# AudioControllerSchematic_Final.net
KiCad netlist of a schematic drawn in EAGLE
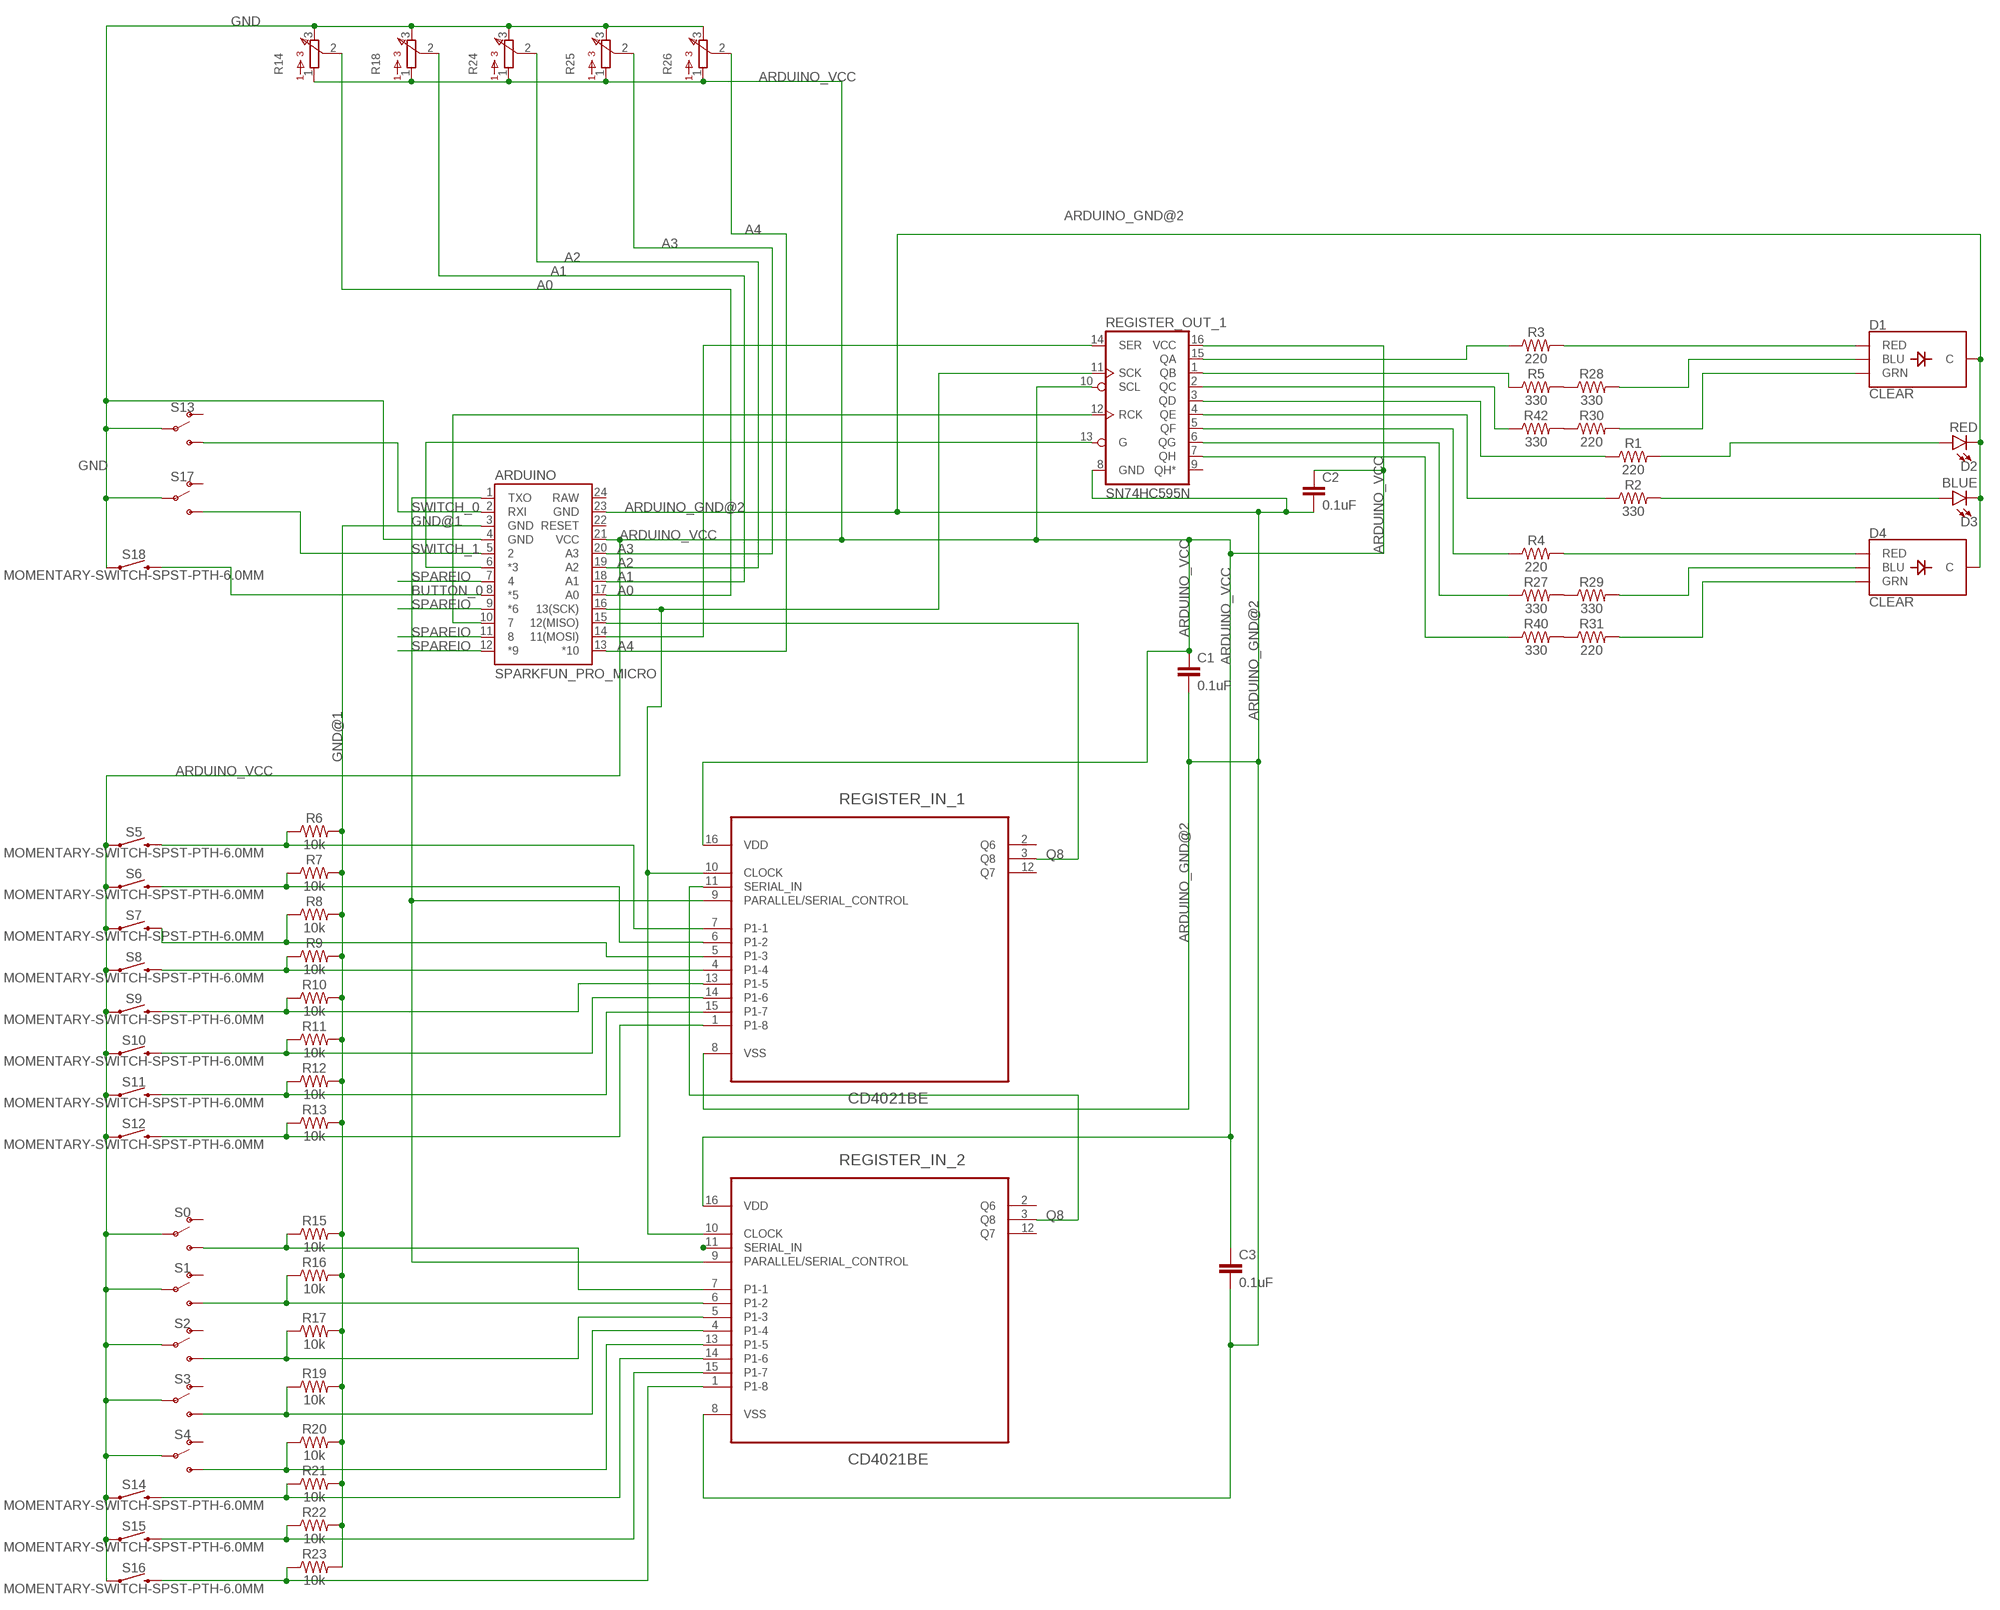
[diagram p0: schematic, sheet 1]

(export (version "E")
  (design (tool "Eeschema 10.0.6"))
  (components
    (comp (ref "ARDUINO")
      (value "SPARKFUN_PRO_MICRO")
      (footprint "eagle-import:SPARKFUN_PRO_MICRO")
      (libsource (lib "eagle-import") (part "SPARKFUN_PRO_MICRO"))
    )
    (comp (ref "C1")
      (value "0.1uF")
      (footprint "eagle-import:0402")
      (libsource (lib "eagle-import") (part "0.1UF-0402-16V-10%"))
    )
    (comp (ref "C2")
      (value "0.1uF")
      (footprint "eagle-import:0402")
      (libsource (lib "eagle-import") (part "0.1UF-0402-16V-10%"))
    )
    (comp (ref "C3")
      (value "0.1uF")
      (footprint "eagle-import:0402")
      (libsource (lib "eagle-import") (part "0.1UF-0402-16V-10%"))
    )
    (comp (ref "D1")
      (value "CLEAR")
      (footprint "eagle-import:LED-RGB-THRU")
      (libsource (lib "eagle-import") (part "LED-RGB-CCCLEAR"))
    )
    (comp (ref "D2")
      (value "RED")
      (footprint "eagle-import:LED-0603")
      (libsource (lib "eagle-import") (part "LED-RED0603"))
    )
    (comp (ref "D3")
      (value "BLUE")
      (footprint "eagle-import:LED-0603")
      (libsource (lib "eagle-import") (part "LED-BLUE0603"))
    )
    (comp (ref "D4")
      (value "CLEAR")
      (footprint "eagle-import:LED-RGB-THRU")
      (libsource (lib "eagle-import") (part "LED-RGB-CCCLEAR"))
    )
    (comp (ref "R1")
      (value "220")
      (footprint "eagle-import:0603")
      (libsource (lib "eagle-import") (part "220OHM-0603-1/10W-1%"))
    )
    (comp (ref "R2")
      (value "330")
      (footprint "eagle-import:0603")
      (libsource (lib "eagle-import") (part "330OHM-0603-1/10W-1%"))
    )
    (comp (ref "R3")
      (value "220")
      (footprint "eagle-import:0603")
      (libsource (lib "eagle-import") (part "220OHM-0603-1/10W-1%"))
    )
    (comp (ref "R4")
      (value "220")
      (footprint "eagle-import:0603")
      (libsource (lib "eagle-import") (part "220OHM-0603-1/10W-1%"))
    )
    (comp (ref "R5")
      (value "330")
      (footprint "eagle-import:0603")
      (libsource (lib "eagle-import") (part "330OHM-0603-1/10W-1%"))
    )
    (comp (ref "R6")
      (value "10k")
      (footprint "eagle-import:0603")
      (libsource (lib "eagle-import") (part "10KOHM-0603-1/10W-1%"))
    )
    (comp (ref "R7")
      (value "10k")
      (footprint "eagle-import:0603")
      (libsource (lib "eagle-import") (part "10KOHM-0603-1/10W-1%"))
    )
    (comp (ref "R8")
      (value "10k")
      (footprint "eagle-import:0603")
      (libsource (lib "eagle-import") (part "10KOHM-0603-1/10W-1%"))
    )
    (comp (ref "R9")
      (value "10k")
      (footprint "eagle-import:0603")
      (libsource (lib "eagle-import") (part "10KOHM-0603-1/10W-1%"))
    )
    (comp (ref "R10")
      (value "10k")
      (footprint "eagle-import:0603")
      (libsource (lib "eagle-import") (part "10KOHM-0603-1/10W-1%"))
    )
    (comp (ref "R11")
      (value "10k")
      (footprint "eagle-import:0603")
      (libsource (lib "eagle-import") (part "10KOHM-0603-1/10W-1%"))
    )
    (comp (ref "R12")
      (value "10k")
      (footprint "eagle-import:0603")
      (libsource (lib "eagle-import") (part "10KOHM-0603-1/10W-1%"))
    )
    (comp (ref "R13")
      (value "10k")
      (footprint "eagle-import:0603")
      (libsource (lib "eagle-import") (part "10KOHM-0603-1/10W-1%"))
    )
    (comp (ref "R14") (value "91") (footprint "eagle-import:91") (libsource (lib "eagle-import") (part "91")))
    (comp (ref "R15")
      (value "10k")
      (footprint "eagle-import:0603")
      (libsource (lib "eagle-import") (part "10KOHM-0603-1/10W-1%"))
    )
    (comp (ref "R16")
      (value "10k")
      (footprint "eagle-import:0603")
      (libsource (lib "eagle-import") (part "10KOHM-0603-1/10W-1%"))
    )
    (comp (ref "R17")
      (value "10k")
      (footprint "eagle-import:0603")
      (libsource (lib "eagle-import") (part "10KOHM-0603-1/10W-1%"))
    )
    (comp (ref "R18") (value "91") (footprint "eagle-import:91") (libsource (lib "eagle-import") (part "91")))
    (comp (ref "R19")
      (value "10k")
      (footprint "eagle-import:0603")
      (libsource (lib "eagle-import") (part "10KOHM-0603-1/10W-1%"))
    )
    (comp (ref "R20")
      (value "10k")
      (footprint "eagle-import:0603")
      (libsource (lib "eagle-import") (part "10KOHM-0603-1/10W-1%"))
    )
    (comp (ref "R21")
      (value "10k")
      (footprint "eagle-import:0603")
      (libsource (lib "eagle-import") (part "10KOHM-0603-1/10W-1%"))
    )
    (comp (ref "R22")
      (value "10k")
      (footprint "eagle-import:0603")
      (libsource (lib "eagle-import") (part "10KOHM-0603-1/10W-1%"))
    )
    (comp (ref "R23")
      (value "10k")
      (footprint "eagle-import:0603")
      (libsource (lib "eagle-import") (part "10KOHM-0603-1/10W-1%"))
    )
    (comp (ref "R24") (value "91") (footprint "eagle-import:91") (libsource (lib "eagle-import") (part "91")))
    (comp (ref "R25") (value "91") (footprint "eagle-import:91") (libsource (lib "eagle-import") (part "91")))
    (comp (ref "R26") (value "91") (footprint "eagle-import:91") (libsource (lib "eagle-import") (part "91")))
    (comp (ref "R27")
      (value "330")
      (footprint "eagle-import:0603")
      (libsource (lib "eagle-import") (part "330OHM-0603-1/10W-1%"))
    )
    (comp (ref "R28")
      (value "330")
      (footprint "eagle-import:0603")
      (libsource (lib "eagle-import") (part "330OHM-0603-1/10W-1%"))
    )
    (comp (ref "R29")
      (value "330")
      (footprint "eagle-import:0603")
      (libsource (lib "eagle-import") (part "330OHM-0603-1/10W-1%"))
    )
    (comp (ref "R30")
      (value "220")
      (footprint "eagle-import:0603")
      (libsource (lib "eagle-import") (part "220OHM-0603-1/10W-1%"))
    )
    (comp (ref "R31")
      (value "220")
      (footprint "eagle-import:0603")
      (libsource (lib "eagle-import") (part "220OHM-0603-1/10W-1%"))
    )
    (comp (ref "R40")
      (value "330")
      (footprint "eagle-import:0603")
      (libsource (lib "eagle-import") (part "330OHM-0603-1/10W-1%"))
    )
    (comp (ref "R42")
      (value "330")
      (footprint "eagle-import:0603")
      (libsource (lib "eagle-import") (part "330OHM-0603-1/10W-1%"))
    )
    (comp (ref "REGISTER_IN_1")
      (value "CD4021BE")
      (footprint "eagle-import:DIP254P762X508-16")
      (fields (field (name "MF") "Texas"))
      (libsource (lib "eagle-import") (part "CD4021BE"))
    )
    (comp (ref "REGISTER_IN_2")
      (value "CD4021BE")
      (footprint "eagle-import:DIP254P762X508-16")
      (fields (field (name "MF") "Texas"))
      (libsource (lib "eagle-import") (part "CD4021BE"))
    )
    (comp (ref "REGISTER_OUT_1")
      (value "SN74HC595N")
      (footprint "eagle-import:DIP16")
      (libsource (lib "eagle-import") (part "74595NHC"))
    )
    (comp (ref "S0")
      (value "SWITCH-SPDT-PTH-11.6X4.0MM")
      (footprint "eagle-import:SWITCH_SPDT_PTH_11.6X4.0MM")
      (libsource (lib "eagle-import") (part "SWITCH-SPDT-PTH-11.6X4.0MM"))
    )
    (comp (ref "S1")
      (value "SWITCH-SPDT-PTH-11.6X4.0MM")
      (footprint "eagle-import:SWITCH_SPDT_PTH_11.6X4.0MM")
      (libsource (lib "eagle-import") (part "SWITCH-SPDT-PTH-11.6X4.0MM"))
    )
    (comp (ref "S2")
      (value "SWITCH-SPDT-PTH-11.6X4.0MM")
      (footprint "eagle-import:SWITCH_SPDT_PTH_11.6X4.0MM")
      (libsource (lib "eagle-import") (part "SWITCH-SPDT-PTH-11.6X4.0MM"))
    )
    (comp (ref "S3")
      (value "SWITCH-SPDT-PTH-11.6X4.0MM")
      (footprint "eagle-import:SWITCH_SPDT_PTH_11.6X4.0MM")
      (libsource (lib "eagle-import") (part "SWITCH-SPDT-PTH-11.6X4.0MM"))
    )
    (comp (ref "S4")
      (value "SWITCH-SPDT-PTH-11.6X4.0MM")
      (footprint "eagle-import:SWITCH_SPDT_PTH_11.6X4.0MM")
      (libsource (lib "eagle-import") (part "SWITCH-SPDT-PTH-11.6X4.0MM"))
    )
    (comp (ref "S5")
      (value "MOMENTARY-SWITCH-SPST-PTH-6.0MM")
      (footprint "eagle-import:TACTILE_SWITCH_PTH_6.0MM")
      (libsource (lib "eagle-import") (part "MOMENTARY-SWITCH-SPST-PTH-6.0MM"))
    )
    (comp (ref "S6")
      (value "MOMENTARY-SWITCH-SPST-PTH-6.0MM")
      (footprint "eagle-import:TACTILE_SWITCH_PTH_6.0MM")
      (libsource (lib "eagle-import") (part "MOMENTARY-SWITCH-SPST-PTH-6.0MM"))
    )
    (comp (ref "S7")
      (value "MOMENTARY-SWITCH-SPST-PTH-6.0MM")
      (footprint "eagle-import:TACTILE_SWITCH_PTH_6.0MM")
      (libsource (lib "eagle-import") (part "MOMENTARY-SWITCH-SPST-PTH-6.0MM"))
    )
    (comp (ref "S8")
      (value "MOMENTARY-SWITCH-SPST-PTH-6.0MM")
      (footprint "eagle-import:TACTILE_SWITCH_PTH_6.0MM")
      (libsource (lib "eagle-import") (part "MOMENTARY-SWITCH-SPST-PTH-6.0MM"))
    )
    (comp (ref "S9")
      (value "MOMENTARY-SWITCH-SPST-PTH-6.0MM")
      (footprint "eagle-import:TACTILE_SWITCH_PTH_6.0MM")
      (libsource (lib "eagle-import") (part "MOMENTARY-SWITCH-SPST-PTH-6.0MM"))
    )
    (comp (ref "S10")
      (value "MOMENTARY-SWITCH-SPST-PTH-6.0MM")
      (footprint "eagle-import:TACTILE_SWITCH_PTH_6.0MM")
      (libsource (lib "eagle-import") (part "MOMENTARY-SWITCH-SPST-PTH-6.0MM"))
    )
    (comp (ref "S11")
      (value "MOMENTARY-SWITCH-SPST-PTH-6.0MM")
      (footprint "eagle-import:TACTILE_SWITCH_PTH_6.0MM")
      (libsource (lib "eagle-import") (part "MOMENTARY-SWITCH-SPST-PTH-6.0MM"))
    )
    (comp (ref "S12")
      (value "MOMENTARY-SWITCH-SPST-PTH-6.0MM")
      (footprint "eagle-import:TACTILE_SWITCH_PTH_6.0MM")
      (libsource (lib "eagle-import") (part "MOMENTARY-SWITCH-SPST-PTH-6.0MM"))
    )
    (comp (ref "S13")
      (value "SWITCH-SPDT-PTH-11.6X4.0MM")
      (footprint "eagle-import:SWITCH_SPDT_PTH_11.6X4.0MM")
      (libsource (lib "eagle-import") (part "SWITCH-SPDT-PTH-11.6X4.0MM"))
    )
    (comp (ref "S14")
      (value "MOMENTARY-SWITCH-SPST-PTH-6.0MM")
      (footprint "eagle-import:TACTILE_SWITCH_PTH_6.0MM")
      (libsource (lib "eagle-import") (part "MOMENTARY-SWITCH-SPST-PTH-6.0MM"))
    )
    (comp (ref "S15")
      (value "MOMENTARY-SWITCH-SPST-PTH-6.0MM")
      (footprint "eagle-import:TACTILE_SWITCH_PTH_6.0MM")
      (libsource (lib "eagle-import") (part "MOMENTARY-SWITCH-SPST-PTH-6.0MM"))
    )
    (comp (ref "S16")
      (value "MOMENTARY-SWITCH-SPST-PTH-6.0MM")
      (footprint "eagle-import:TACTILE_SWITCH_PTH_6.0MM")
      (libsource (lib "eagle-import") (part "MOMENTARY-SWITCH-SPST-PTH-6.0MM"))
    )
    (comp (ref "S17")
      (value "SWITCH-SPDT-PTH-11.6X4.0MM")
      (footprint "eagle-import:SWITCH_SPDT_PTH_11.6X4.0MM")
      (libsource (lib "eagle-import") (part "SWITCH-SPDT-PTH-11.6X4.0MM"))
    )
    (comp (ref "S18")
      (value "MOMENTARY-SWITCH-SPST-PTH-6.0MM")
      (footprint "eagle-import:TACTILE_SWITCH_PTH_6.0MM")
      (libsource (lib "eagle-import") (part "MOMENTARY-SWITCH-SPST-PTH-6.0MM"))
    )
  )
  (nets
    (net (code "1") (name "/A0") (class "Default")
      (node (ref "ARDUINO") (pin "17") (pinfunction "A0_17") (pintype "bidirectional"))
      (node (ref "R14") (pin "2") (pinfunction "2_2") (pintype "passive"))
    )
    (net (code "2") (name "/A1") (class "Default")
      (node (ref "ARDUINO") (pin "18") (pinfunction "A1_18") (pintype "bidirectional"))
      (node (ref "R18") (pin "2") (pinfunction "2_2") (pintype "passive"))
    )
    (net (code "3") (name "/A2") (class "Default")
      (node (ref "ARDUINO") (pin "19") (pinfunction "A2_19") (pintype "bidirectional"))
      (node (ref "R24") (pin "2") (pinfunction "2_2") (pintype "passive"))
    )
    (net (code "4") (name "/A3") (class "Default")
      (node (ref "ARDUINO") (pin "20") (pinfunction "A3_20") (pintype "bidirectional"))
      (node (ref "R25") (pin "2") (pinfunction "2_2") (pintype "passive"))
    )
    (net (code "5") (name "/A4") (class "Default")
      (node (ref "ARDUINO") (pin "13") (pinfunction "*10_13") (pintype "bidirectional"))
      (node (ref "R26") (pin "2") (pinfunction "2_2") (pintype "passive"))
    )
    (net (code "6") (name "/ARDUINO_GND@2") (class "Default")
      (node (ref "ARDUINO") (pin "23") (pinfunction "GND_23") (pintype "power_in"))
      (node (ref "C1") (pin "2") (pinfunction "2_2") (pintype "passive"))
      (node (ref "C2") (pin "2") (pinfunction "2_2") (pintype "passive"))
      (node (ref "C3") (pin "2") (pinfunction "2_2") (pintype "passive"))
      (node (ref "D1") (pin "2") (pinfunction "C_2") (pintype "bidirectional"))
      (node (ref "D2") (pin "C") (pinfunction "C_C") (pintype "passive"))
      (node (ref "D3") (pin "C") (pinfunction "C_C") (pintype "passive"))
      (node (ref "D4") (pin "2") (pinfunction "C_2") (pintype "bidirectional"))
      (node (ref "REGISTER_IN_1") (pin "8") (pinfunction "VSS_8") (pintype "passive"))
      (node (ref "REGISTER_IN_2") (pin "8") (pinfunction "VSS_8") (pintype "passive"))
      (node (ref "REGISTER_OUT_1") (pin "8") (pinfunction "GND_8") (pintype "power_in"))
    )
    (net (code "7") (name "/ARDUINO_VCC") (class "Default")
      (node (ref "ARDUINO") (pin "21") (pinfunction "VCC_21") (pintype "power_in"))
      (node (ref "C1") (pin "1") (pinfunction "1_1") (pintype "passive"))
      (node (ref "C2") (pin "1") (pinfunction "1_1") (pintype "passive"))
      (node (ref "C3") (pin "1") (pinfunction "1_1") (pintype "passive"))
      (node (ref "R14") (pin "1") (pinfunction "1_1") (pintype "passive"))
      (node (ref "R18") (pin "1") (pinfunction "1_1") (pintype "passive"))
      (node (ref "R24") (pin "1") (pinfunction "1_1") (pintype "passive"))
      (node (ref "R25") (pin "1") (pinfunction "1_1") (pintype "passive"))
      (node (ref "R26") (pin "1") (pinfunction "1_1") (pintype "passive"))
      (node (ref "REGISTER_IN_1") (pin "16") (pinfunction "VDD_16") (pintype "power_in"))
      (node (ref "REGISTER_IN_2") (pin "16") (pinfunction "VDD_16") (pintype "power_in"))
      (node (ref "REGISTER_OUT_1") (pin "10") (pinfunction "SCL_10") (pintype "input"))
      (node (ref "REGISTER_OUT_1") (pin "16") (pinfunction "VCC_16") (pintype "power_in"))
      (node (ref "S0") (pin "2") (pinfunction "P_2") (pintype "passive"))
      (node (ref "S1") (pin "2") (pinfunction "P_2") (pintype "passive"))
      (node (ref "S10") (pin "1") (pinfunction "1_1") (pintype "passive"))
      (node (ref "S11") (pin "1") (pinfunction "1_1") (pintype "passive"))
      (node (ref "S12") (pin "1") (pinfunction "1_1") (pintype "passive"))
      (node (ref "S14") (pin "1") (pinfunction "1_1") (pintype "passive"))
      (node (ref "S15") (pin "1") (pinfunction "1_1") (pintype "passive"))
      (node (ref "S16") (pin "1") (pinfunction "1_1") (pintype "passive"))
      (node (ref "S2") (pin "2") (pinfunction "P_2") (pintype "passive"))
      (node (ref "S3") (pin "2") (pinfunction "P_2") (pintype "passive"))
      (node (ref "S4") (pin "2") (pinfunction "P_2") (pintype "passive"))
      (node (ref "S5") (pin "1") (pinfunction "1_1") (pintype "passive"))
      (node (ref "S6") (pin "1") (pinfunction "1_1") (pintype "passive"))
      (node (ref "S7") (pin "1") (pinfunction "1_1") (pintype "passive"))
      (node (ref "S8") (pin "1") (pinfunction "1_1") (pintype "passive"))
      (node (ref "S9") (pin "1") (pinfunction "1_1") (pintype "passive"))
    )
    (net (code "8") (name "/BUTTON_0") (class "Default")
      (node (ref "ARDUINO") (pin "8") (pinfunction "*5_8") (pintype "bidirectional"))
      (node (ref "S18") (pin "3") (pinfunction "2_3") (pintype "passive"))
    )
    (net (code "9") (name "/GND") (class "Default")
      (node (ref "ARDUINO") (pin "4") (pinfunction "GND_4") (pintype "power_in"))
      (node (ref "R14") (pin "3") (pinfunction "3_3") (pintype "passive"))
      (node (ref "R18") (pin "3") (pinfunction "3_3") (pintype "passive"))
      (node (ref "R24") (pin "3") (pinfunction "3_3") (pintype "passive"))
      (node (ref "R25") (pin "3") (pinfunction "3_3") (pintype "passive"))
      (node (ref "R26") (pin "3") (pinfunction "3_3") (pintype "passive"))
      (node (ref "S13") (pin "2") (pinfunction "P_2") (pintype "passive"))
      (node (ref "S17") (pin "2") (pinfunction "P_2") (pintype "passive"))
      (node (ref "S18") (pin "1") (pinfunction "1_1") (pintype "passive"))
    )
    (net (code "10") (name "/GND@1") (class "Default")
      (node (ref "ARDUINO") (pin "3") (pinfunction "GND_3") (pintype "power_in"))
      (node (ref "R10") (pin "2") (pinfunction "2_2") (pintype "passive"))
      (node (ref "R11") (pin "2") (pinfunction "2_2") (pintype "passive"))
      (node (ref "R12") (pin "2") (pinfunction "2_2") (pintype "passive"))
      (node (ref "R13") (pin "2") (pinfunction "2_2") (pintype "passive"))
      (node (ref "R15") (pin "2") (pinfunction "2_2") (pintype "passive"))
      (node (ref "R16") (pin "2") (pinfunction "2_2") (pintype "passive"))
      (node (ref "R17") (pin "2") (pinfunction "2_2") (pintype "passive"))
      (node (ref "R19") (pin "2") (pinfunction "2_2") (pintype "passive"))
      (node (ref "R20") (pin "2") (pinfunction "2_2") (pintype "passive"))
      (node (ref "R21") (pin "2") (pinfunction "2_2") (pintype "passive"))
      (node (ref "R22") (pin "2") (pinfunction "2_2") (pintype "passive"))
      (node (ref "R23") (pin "2") (pinfunction "2_2") (pintype "passive"))
      (node (ref "R6") (pin "2") (pinfunction "2_2") (pintype "passive"))
      (node (ref "R7") (pin "2") (pinfunction "2_2") (pintype "passive"))
      (node (ref "R8") (pin "2") (pinfunction "2_2") (pintype "passive"))
      (node (ref "R9") (pin "2") (pinfunction "2_2") (pintype "passive"))
    )
    (net (code "11") (name "/Q8") (class "Default")
      (node (ref "ARDUINO") (pin "15") (pinfunction "12(MISO)_15") (pintype "bidirectional"))
      (node (ref "REGISTER_IN_1") (pin "11") (pinfunction "SERIAL_IN_11") (pintype "input"))
      (node (ref "REGISTER_IN_1") (pin "3") (pinfunction "Q8_3") (pintype "output"))
      (node (ref "REGISTER_IN_2") (pin "3") (pinfunction "Q8_3") (pintype "output"))
    )
    (net (code "12") (name "/RAW") (class "Default")
      (node (ref "ARDUINO") (pin "24") (pinfunction "RAW_24") (pintype "power_in"))
    )
    (net (code "13") (name "/SPAREIO") (class "Default")
      (node (ref "ARDUINO") (pin "11") (pinfunction "8_11") (pintype "bidirectional"))
      (node (ref "ARDUINO") (pin "12") (pinfunction "*9_12") (pintype "bidirectional"))
      (node (ref "ARDUINO") (pin "7") (pinfunction "4_7") (pintype "bidirectional"))
      (node (ref "ARDUINO") (pin "9") (pinfunction "*6_9") (pintype "bidirectional"))
    )
    (net (code "14") (name "/SWITCH_0") (class "Default")
      (node (ref "ARDUINO") (pin "2") (pinfunction "RXI_2") (pintype "bidirectional"))
      (node (ref "S13") (pin "3") (pinfunction "S_3") (pintype "passive"))
    )
    (net (code "15") (name "/SWITCH_1") (class "Default")
      (node (ref "ARDUINO") (pin "5") (pinfunction "2_5") (pintype "bidirectional"))
      (node (ref "S17") (pin "3") (pinfunction "S_3") (pintype "passive"))
    )
    (net (code "16") (name "Net-(ARDUINO-*3)") (class "Default")
      (node (ref "ARDUINO") (pin "6") (pinfunction "*3_6") (pintype "bidirectional"))
      (node (ref "REGISTER_OUT_1") (pin "13") (pinfunction "G_13") (pintype "input"))
    )
    (net (code "17") (name "Net-(ARDUINO-7)") (class "Default")
      (node (ref "ARDUINO") (pin "10") (pinfunction "7_10") (pintype "bidirectional"))
      (node (ref "REGISTER_OUT_1") (pin "12") (pinfunction "RCK_12") (pintype "input"))
    )
    (net (code "18") (name "Net-(ARDUINO-11(MOSI))") (class "Default")
      (node (ref "ARDUINO") (pin "14") (pinfunction "11(MOSI)_14") (pintype "bidirectional"))
      (node (ref "REGISTER_OUT_1") (pin "14") (pinfunction "SER_14") (pintype "input"))
    )
    (net (code "19") (name "Net-(ARDUINO-13(SCK))") (class "Default")
      (node (ref "ARDUINO") (pin "16") (pinfunction "13(SCK)_16") (pintype "bidirectional"))
      (node (ref "REGISTER_IN_1") (pin "10") (pinfunction "CLOCK_10") (pintype "input"))
      (node (ref "REGISTER_IN_2") (pin "10") (pinfunction "CLOCK_10") (pintype "input"))
      (node (ref "REGISTER_OUT_1") (pin "11") (pinfunction "SCK_11") (pintype "input"))
    )
    (net (code "20") (name "Net-(ARDUINO-TXO)") (class "Default")
      (node (ref "ARDUINO") (pin "1") (pinfunction "TXO_1") (pintype "bidirectional"))
      (node (ref "REGISTER_IN_1") (pin "9") (pinfunction "PARALLEL/SERIAL_CONTROL_9") (pintype "input"))
      (node (ref "REGISTER_IN_2") (pin "9") (pinfunction "PARALLEL/SERIAL_CONTROL_9") (pintype "input"))
    )
    (net (code "21") (name "Net-(D1-BLU)") (class "Default")
      (node (ref "D1") (pin "4") (pinfunction "BLU_4") (pintype "bidirectional"))
      (node (ref "R28") (pin "2") (pinfunction "2_2") (pintype "passive"))
    )
    (net (code "22") (name "Net-(D1-GRN)") (class "Default")
      (node (ref "D1") (pin "3") (pinfunction "GRN_3") (pintype "bidirectional"))
      (node (ref "R30") (pin "2") (pinfunction "2_2") (pintype "passive"))
    )
    (net (code "23") (name "Net-(D1-RED)") (class "Default")
      (node (ref "D1") (pin "1") (pinfunction "RED_1") (pintype "bidirectional"))
      (node (ref "R3") (pin "2") (pinfunction "2_2") (pintype "passive"))
    )
    (net (code "24") (name "Net-(D2-PadA)") (class "Default")
      (node (ref "D2") (pin "A") (pinfunction "A_A") (pintype "passive"))
      (node (ref "R1") (pin "2") (pinfunction "2_2") (pintype "passive"))
    )
    (net (code "25") (name "Net-(D3-PadA)") (class "Default")
      (node (ref "D3") (pin "A") (pinfunction "A_A") (pintype "passive"))
      (node (ref "R2") (pin "2") (pinfunction "2_2") (pintype "passive"))
    )
    (net (code "26") (name "Net-(D4-BLU)") (class "Default")
      (node (ref "D4") (pin "4") (pinfunction "BLU_4") (pintype "bidirectional"))
      (node (ref "R29") (pin "2") (pinfunction "2_2") (pintype "passive"))
    )
    (net (code "27") (name "Net-(D4-GRN)") (class "Default")
      (node (ref "D4") (pin "3") (pinfunction "GRN_3") (pintype "bidirectional"))
      (node (ref "R31") (pin "2") (pinfunction "2_2") (pintype "passive"))
    )
    (net (code "28") (name "Net-(D4-RED)") (class "Default")
      (node (ref "D4") (pin "1") (pinfunction "RED_1") (pintype "bidirectional"))
      (node (ref "R4") (pin "2") (pinfunction "2_2") (pintype "passive"))
    )
    (net (code "29") (name "Net-(R27-Pad2)") (class "Default")
      (node (ref "R27") (pin "2") (pinfunction "2_2") (pintype "passive"))
      (node (ref "R29") (pin "1") (pinfunction "1_1") (pintype "passive"))
    )
    (net (code "30") (name "Net-(R28-Pad1)") (class "Default")
      (node (ref "R28") (pin "1") (pinfunction "1_1") (pintype "passive"))
      (node (ref "R5") (pin "2") (pinfunction "2_2") (pintype "passive"))
    )
    (net (code "31") (name "Net-(R30-Pad1)") (class "Default")
      (node (ref "R30") (pin "1") (pinfunction "1_1") (pintype "passive"))
      (node (ref "R42") (pin "2") (pinfunction "2_2") (pintype "passive"))
    )
    (net (code "32") (name "Net-(R31-Pad1)") (class "Default")
      (node (ref "R31") (pin "1") (pinfunction "1_1") (pintype "passive"))
      (node (ref "R40") (pin "2") (pinfunction "2_2") (pintype "passive"))
    )
    (net (code "33") (name "Net-(REGISTER_IN_1-P1-1)") (class "Default")
      (node (ref "R6") (pin "1") (pinfunction "1_1") (pintype "passive"))
      (node (ref "REGISTER_IN_1") (pin "7") (pinfunction "P1-1_7") (pintype "input"))
      (node (ref "S5") (pin "3") (pinfunction "2_3") (pintype "passive"))
    )
    (net (code "34") (name "Net-(REGISTER_IN_1-P1-2)") (class "Default")
      (node (ref "R7") (pin "1") (pinfunction "1_1") (pintype "passive"))
      (node (ref "REGISTER_IN_1") (pin "6") (pinfunction "P1-2_6") (pintype "input"))
      (node (ref "S6") (pin "3") (pinfunction "2_3") (pintype "passive"))
    )
    (net (code "35") (name "Net-(REGISTER_IN_1-P1-3)") (class "Default")
      (node (ref "R8") (pin "1") (pinfunction "1_1") (pintype "passive"))
      (node (ref "REGISTER_IN_1") (pin "5") (pinfunction "P1-3_5") (pintype "input"))
      (node (ref "S7") (pin "3") (pinfunction "2_3") (pintype "passive"))
    )
    (net (code "36") (name "Net-(REGISTER_IN_1-P1-4)") (class "Default")
      (node (ref "R9") (pin "1") (pinfunction "1_1") (pintype "passive"))
      (node (ref "REGISTER_IN_1") (pin "4") (pinfunction "P1-4_4") (pintype "input"))
      (node (ref "S8") (pin "3") (pinfunction "2_3") (pintype "passive"))
    )
    (net (code "37") (name "Net-(REGISTER_IN_1-P1-5)") (class "Default")
      (node (ref "R10") (pin "1") (pinfunction "1_1") (pintype "passive"))
      (node (ref "REGISTER_IN_1") (pin "13") (pinfunction "P1-5_13") (pintype "input"))
      (node (ref "S9") (pin "3") (pinfunction "2_3") (pintype "passive"))
    )
    (net (code "38") (name "Net-(REGISTER_IN_1-P1-6)") (class "Default")
      (node (ref "R11") (pin "1") (pinfunction "1_1") (pintype "passive"))
      (node (ref "REGISTER_IN_1") (pin "14") (pinfunction "P1-6_14") (pintype "input"))
      (node (ref "S10") (pin "3") (pinfunction "2_3") (pintype "passive"))
    )
    (net (code "39") (name "Net-(REGISTER_IN_1-P1-7)") (class "Default")
      (node (ref "R12") (pin "1") (pinfunction "1_1") (pintype "passive"))
      (node (ref "REGISTER_IN_1") (pin "15") (pinfunction "P1-7_15") (pintype "input"))
      (node (ref "S11") (pin "3") (pinfunction "2_3") (pintype "passive"))
    )
    (net (code "40") (name "Net-(REGISTER_IN_1-P1-8)") (class "Default")
      (node (ref "R13") (pin "1") (pinfunction "1_1") (pintype "passive"))
      (node (ref "REGISTER_IN_1") (pin "1") (pinfunction "P1-8_1") (pintype "input"))
      (node (ref "S12") (pin "3") (pinfunction "2_3") (pintype "passive"))
    )
    (net (code "41") (name "Net-(REGISTER_IN_2-P1-1)") (class "Default")
      (node (ref "R15") (pin "1") (pinfunction "1_1") (pintype "passive"))
      (node (ref "REGISTER_IN_2") (pin "7") (pinfunction "P1-1_7") (pintype "input"))
      (node (ref "S0") (pin "3") (pinfunction "S_3") (pintype "passive"))
    )
    (net (code "42") (name "Net-(REGISTER_IN_2-P1-2)") (class "Default")
      (node (ref "R16") (pin "1") (pinfunction "1_1") (pintype "passive"))
      (node (ref "REGISTER_IN_2") (pin "6") (pinfunction "P1-2_6") (pintype "input"))
      (node (ref "S1") (pin "3") (pinfunction "S_3") (pintype "passive"))
    )
    (net (code "43") (name "Net-(REGISTER_IN_2-P1-3)") (class "Default")
      (node (ref "R17") (pin "1") (pinfunction "1_1") (pintype "passive"))
      (node (ref "REGISTER_IN_2") (pin "5") (pinfunction "P1-3_5") (pintype "input"))
      (node (ref "S2") (pin "3") (pinfunction "S_3") (pintype "passive"))
    )
    (net (code "44") (name "Net-(REGISTER_IN_2-P1-4)") (class "Default")
      (node (ref "R19") (pin "1") (pinfunction "1_1") (pintype "passive"))
      (node (ref "REGISTER_IN_2") (pin "4") (pinfunction "P1-4_4") (pintype "input"))
      (node (ref "S3") (pin "3") (pinfunction "S_3") (pintype "passive"))
    )
    (net (code "45") (name "Net-(REGISTER_IN_2-P1-5)") (class "Default")
      (node (ref "R20") (pin "1") (pinfunction "1_1") (pintype "passive"))
      (node (ref "REGISTER_IN_2") (pin "13") (pinfunction "P1-5_13") (pintype "input"))
      (node (ref "S4") (pin "3") (pinfunction "S_3") (pintype "passive"))
    )
    (net (code "46") (name "Net-(REGISTER_IN_2-P1-6)") (class "Default")
      (node (ref "R21") (pin "1") (pinfunction "1_1") (pintype "passive"))
      (node (ref "REGISTER_IN_2") (pin "14") (pinfunction "P1-6_14") (pintype "input"))
      (node (ref "S14") (pin "3") (pinfunction "2_3") (pintype "passive"))
    )
    (net (code "47") (name "Net-(REGISTER_IN_2-P1-7)") (class "Default")
      (node (ref "R22") (pin "1") (pinfunction "1_1") (pintype "passive"))
      (node (ref "REGISTER_IN_2") (pin "15") (pinfunction "P1-7_15") (pintype "input"))
      (node (ref "S15") (pin "3") (pinfunction "2_3") (pintype "passive"))
    )
    (net (code "48") (name "Net-(REGISTER_IN_2-P1-8)") (class "Default")
      (node (ref "R23") (pin "1") (pinfunction "1_1") (pintype "passive"))
      (node (ref "REGISTER_IN_2") (pin "1") (pinfunction "P1-8_1") (pintype "input"))
      (node (ref "S16") (pin "3") (pinfunction "2_3") (pintype "passive"))
    )
    (net (code "49") (name "Net-(REGISTER_OUT_1-QA)") (class "Default")
      (node (ref "R3") (pin "1") (pinfunction "1_1") (pintype "passive"))
      (node (ref "REGISTER_OUT_1") (pin "15") (pinfunction "QA_15") (pintype "tri_state"))
    )
    (net (code "50") (name "Net-(REGISTER_OUT_1-QB)") (class "Default")
      (node (ref "R5") (pin "1") (pinfunction "1_1") (pintype "passive"))
      (node (ref "REGISTER_OUT_1") (pin "1") (pinfunction "QB_1") (pintype "tri_state"))
    )
    (net (code "51") (name "Net-(REGISTER_OUT_1-QC)") (class "Default")
      (node (ref "R42") (pin "1") (pinfunction "1_1") (pintype "passive"))
      (node (ref "REGISTER_OUT_1") (pin "2") (pinfunction "QC_2") (pintype "tri_state"))
    )
    (net (code "52") (name "Net-(REGISTER_OUT_1-QD)") (class "Default")
      (node (ref "R1") (pin "1") (pinfunction "1_1") (pintype "passive"))
      (node (ref "REGISTER_OUT_1") (pin "3") (pinfunction "QD_3") (pintype "tri_state"))
    )
    (net (code "53") (name "Net-(REGISTER_OUT_1-QE)") (class "Default")
      (node (ref "R2") (pin "1") (pinfunction "1_1") (pintype "passive"))
      (node (ref "REGISTER_OUT_1") (pin "4") (pinfunction "QE_4") (pintype "tri_state"))
    )
    (net (code "54") (name "Net-(REGISTER_OUT_1-QF)") (class "Default")
      (node (ref "R4") (pin "1") (pinfunction "1_1") (pintype "passive"))
      (node (ref "REGISTER_OUT_1") (pin "5") (pinfunction "QF_5") (pintype "tri_state"))
    )
    (net (code "55") (name "Net-(REGISTER_OUT_1-QG)") (class "Default")
      (node (ref "R27") (pin "1") (pinfunction "1_1") (pintype "passive"))
      (node (ref "REGISTER_OUT_1") (pin "6") (pinfunction "QG_6") (pintype "tri_state"))
    )
    (net (code "56") (name "Net-(REGISTER_OUT_1-QH)") (class "Default")
      (node (ref "R40") (pin "1") (pinfunction "1_1") (pintype "passive"))
      (node (ref "REGISTER_OUT_1") (pin "7") (pinfunction "QH_7") (pintype "tri_state"))
    )
    (net (code "57") (name "unconnected-(ARDUINO-RESET-Pad22)") (class "Default")
      (node (ref "ARDUINO") (pin "22") (pinfunction "RESET_22") (pintype "bidirectional"))
    )
    (net (code "58") (name "unconnected-(REGISTER_IN_1-Q6-Pad2)") (class "Default")
      (node (ref "REGISTER_IN_1") (pin "2") (pinfunction "Q6_2") (pintype "output"))
    )
    (net (code "59") (name "unconnected-(REGISTER_IN_1-Q7-Pad12)") (class "Default")
      (node (ref "REGISTER_IN_1") (pin "12") (pinfunction "Q7_12") (pintype "output"))
    )
    (net (code "60") (name "unconnected-(REGISTER_IN_2-Q6-Pad2)") (class "Default")
      (node (ref "REGISTER_IN_2") (pin "2") (pinfunction "Q6_2") (pintype "output"))
    )
    (net (code "61") (name "unconnected-(REGISTER_IN_2-Q7-Pad12)") (class "Default")
      (node (ref "REGISTER_IN_2") (pin "12") (pinfunction "Q7_12") (pintype "output"))
    )
    (net (code "62") (name "unconnected-(REGISTER_IN_2-SERIAL_IN-Pad11)") (class "Default")
      (node (ref "REGISTER_IN_2") (pin "11") (pinfunction "SERIAL_IN_11") (pintype "input"))
    )
    (net (code "63") (name "unconnected-(REGISTER_OUT_1-QH*-Pad9)") (class "Default")
      (node (ref "REGISTER_OUT_1") (pin "9") (pinfunction "QH*_9") (pintype "tri_state"))
    )
    (net (code "64") (name "unconnected-(S0-O-Pad1)") (class "Default")
      (node (ref "S0") (pin "1") (pinfunction "O_1") (pintype "passive"))
    )
    (net (code "65") (name "unconnected-(S1-O-Pad1)") (class "Default")
      (node (ref "S1") (pin "1") (pinfunction "O_1") (pintype "passive"))
    )
    (net (code "66") (name "unconnected-(S2-O-Pad1)") (class "Default")
      (node (ref "S2") (pin "1") (pinfunction "O_1") (pintype "passive"))
    )
    (net (code "67") (name "unconnected-(S3-O-Pad1)") (class "Default")
      (node (ref "S3") (pin "1") (pinfunction "O_1") (pintype "passive"))
    )
    (net (code "68") (name "unconnected-(S4-O-Pad1)") (class "Default")
      (node (ref "S4") (pin "1") (pinfunction "O_1") (pintype "passive"))
    )
    (net (code "69") (name "unconnected-(S13-O-Pad1)") (class "Default")
      (node (ref "S13") (pin "1") (pinfunction "O_1") (pintype "passive"))
    )
    (net (code "70") (name "unconnected-(S17-O-Pad1)") (class "Default")
      (node (ref "S17") (pin "1") (pinfunction "O_1") (pintype "passive"))
    )
  )
)
